# MCU.net
KiCad netlist of a schematic drawn in Altium Designer
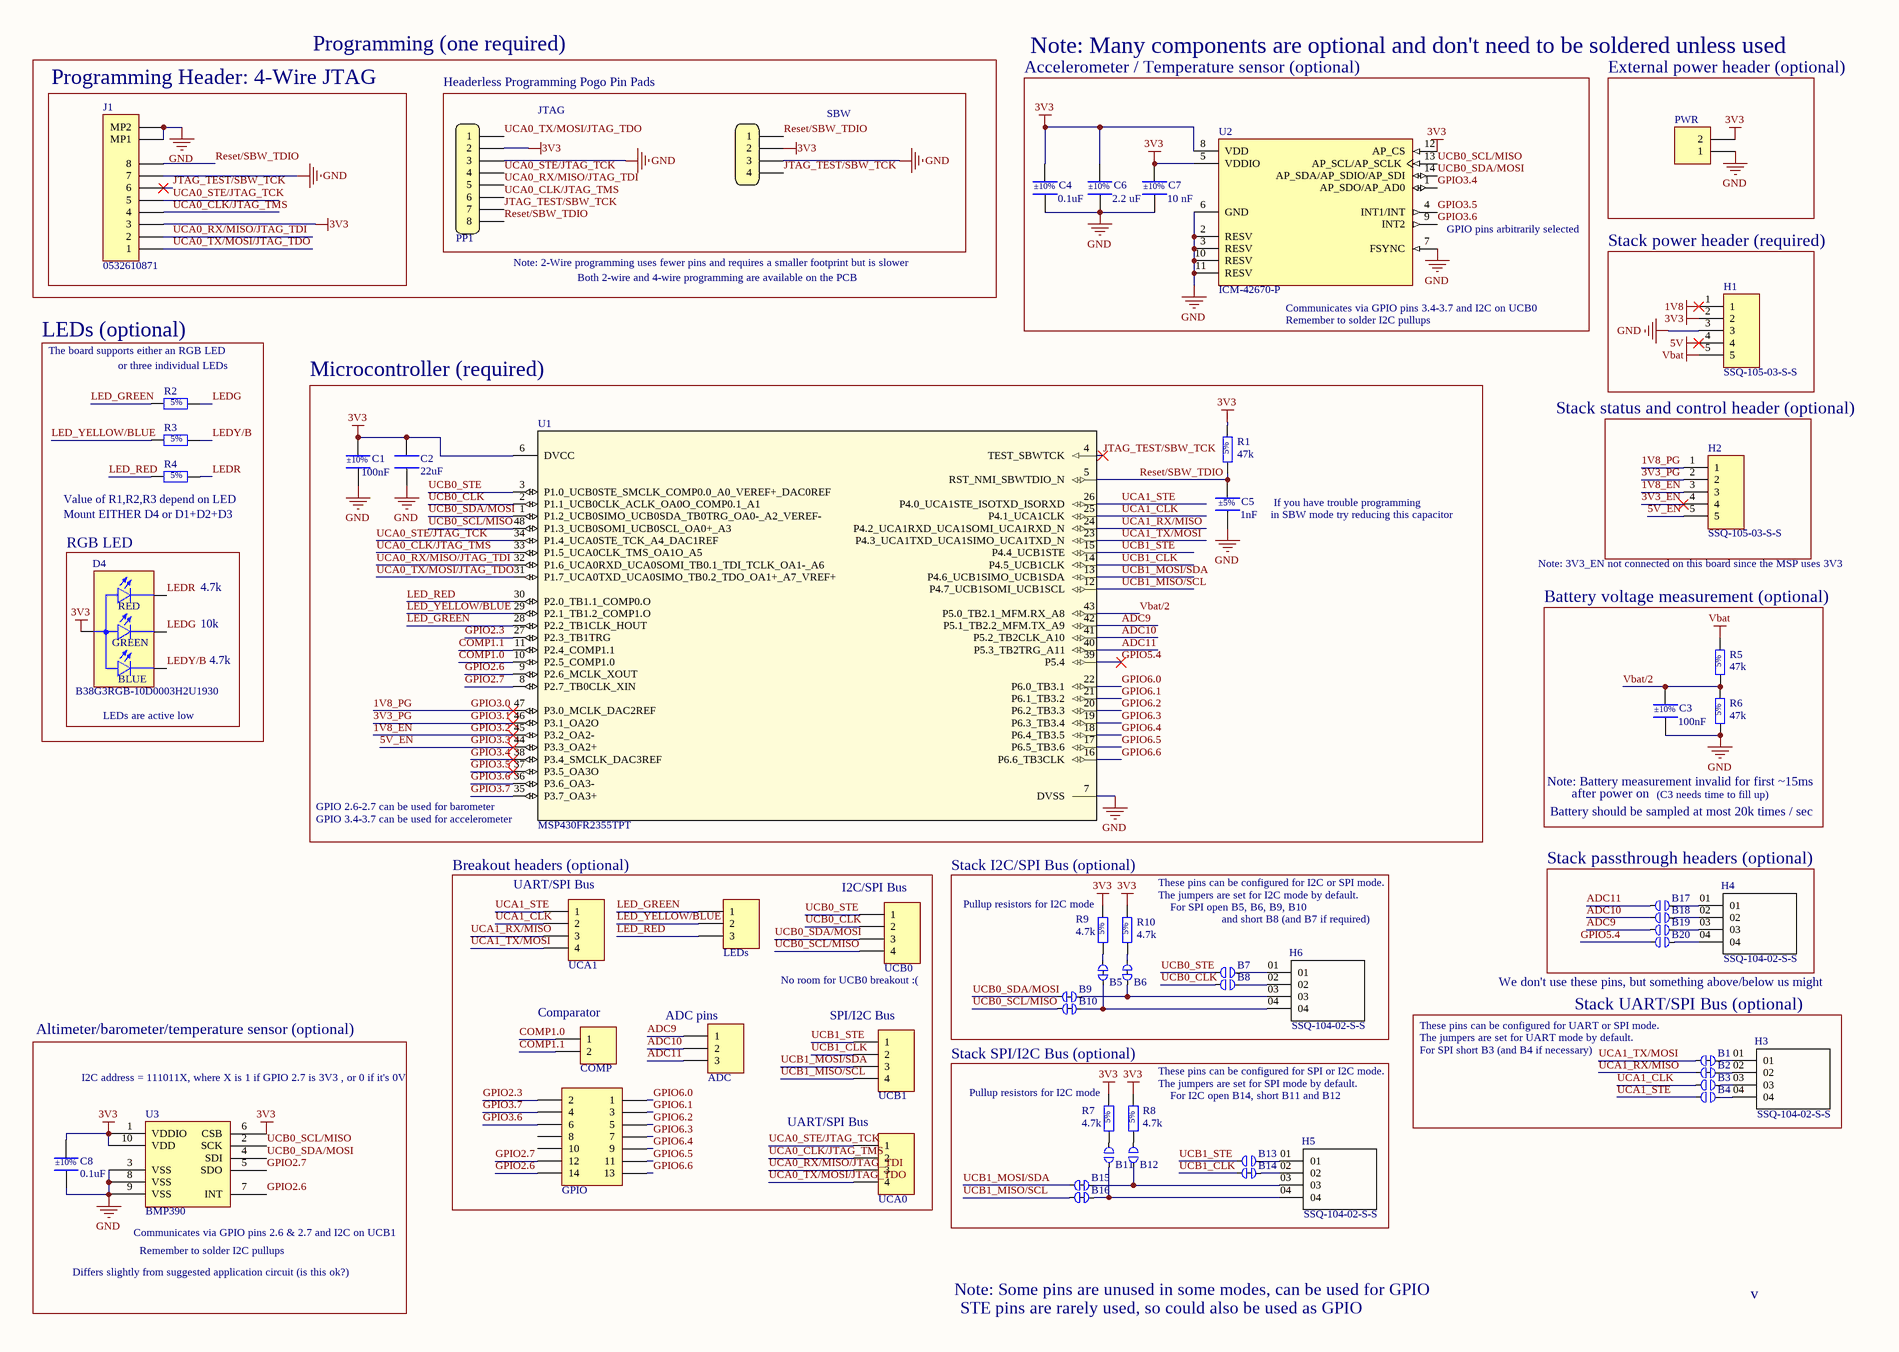
[diagram p0: MCU.SchDoc, left]
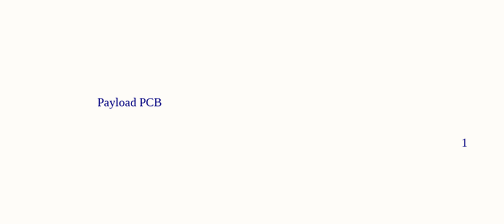
[diagram p1: MCU.SchDoc, right]

(export (version "E")
  (design (tool "Eeschema 10.0.6"))
  (components
    (comp (ref "ADC")
      (value "Header 3")
      (footprint "HDR1X3")
      (description "Header, 3-Pin")
      (libsource (lib "Miscellaneous Connectors") (part "Header 3"))
    )
    (comp (ref "B1")
      (value "Solder Jumper Normally Closed 0201")
      (footprint "Solder Bridge Closed 0201")
      (libsource (lib "APSS Generic Components") (part "Solder Jumper Normally Closed 0201"))
    )
    (comp (ref "B2")
      (value "Solder Jumper Normally Closed 0201")
      (footprint "Solder Bridge Closed 0201")
      (libsource (lib "APSS Generic Components") (part "Solder Jumper Normally Closed 0201"))
    )
    (comp (ref "B3")
      (value "Solder Jumper Normally Open 0201")
      (footprint "Solder Bridge Open 0201")
      (libsource (lib "APSS Generic Components") (part "Solder Jumper Normally Open 0201"))
    )
    (comp (ref "B4")
      (value "Solder Jumper Normally Open 0201")
      (footprint "Solder Bridge Open 0201")
      (libsource (lib "APSS Generic Components") (part "Solder Jumper Normally Open 0201"))
    )
    (comp (ref "B5")
      (value "Solder Jumper Normally Closed 0201")
      (footprint "Solder Bridge Closed 0201")
      (libsource (lib "APSS Generic Components") (part "Solder Jumper Normally Closed 0201"))
    )
    (comp (ref "B6")
      (value "Solder Jumper Normally Closed 0201")
      (footprint "Solder Bridge Closed 0201")
      (libsource (lib "APSS Generic Components") (part "Solder Jumper Normally Closed 0201"))
    )
    (comp (ref "B7")
      (value "Solder Jumper Normally Open 0201")
      (footprint "Solder Bridge Open 0201")
      (libsource (lib "") (part "Solder Jumper Normally Open 0201_1"))
    )
    (comp (ref "B8")
      (value "Solder Jumper Normally Open 0201")
      (footprint "Solder Bridge Open 0201")
      (libsource (lib "") (part "Solder Jumper Normally Open 0201_1"))
    )
    (comp (ref "B9")
      (value "Solder Jumper Normally Closed 0201")
      (footprint "Solder Bridge Closed 0201")
      (libsource (lib "APSS Generic Components") (part "Solder Jumper Normally Closed 0201"))
    )
    (comp (ref "B10")
      (value "Solder Jumper Normally Closed 0201")
      (footprint "Solder Bridge Closed 0201")
      (libsource (lib "APSS Generic Components") (part "Solder Jumper Normally Closed 0201"))
    )
    (comp (ref "B11")
      (value "Solder Jumper Normally Open 0201")
      (footprint "Solder Bridge Open 0201")
      (libsource (lib "APSS Generic Components") (part "Solder Jumper Normally Open 0201"))
    )
    (comp (ref "B12")
      (value "Solder Jumper Normally Open 0201")
      (footprint "Solder Bridge Open 0201")
      (libsource (lib "APSS Generic Components") (part "Solder Jumper Normally Open 0201"))
    )
    (comp (ref "B13")
      (value "Solder Jumper Normally Open 0201")
      (footprint "Solder Bridge Open 0201")
      (libsource (lib "APSS Generic Components") (part "Solder Jumper Normally Open 0201"))
    )
    (comp (ref "B14")
      (value "Solder Jumper Normally Closed 0201")
      (footprint "Solder Bridge Closed 0201")
      (libsource (lib "APSS Generic Components") (part "Solder Jumper Normally Closed 0201"))
    )
    (comp (ref "B15")
      (value "Solder Jumper Normally Closed 0201")
      (footprint "Solder Bridge Closed 0201")
      (libsource (lib "APSS Generic Components") (part "Solder Jumper Normally Closed 0201"))
    )
    (comp (ref "B16")
      (value "Solder Jumper Normally Closed 0201")
      (footprint "Solder Bridge Closed 0201")
      (libsource (lib "APSS Generic Components") (part "Solder Jumper Normally Closed 0201"))
    )
    (comp (ref "B17")
      (value "Solder Jumper Normally Open 0201")
      (footprint "Solder Bridge Open 0201")
      (libsource (lib "APSS Generic Components") (part "Solder Jumper Normally Open 0201"))
    )
    (comp (ref "B18")
      (value "Solder Jumper Normally Open 0201")
      (footprint "Solder Bridge Open 0201")
      (libsource (lib "APSS Generic Components") (part "Solder Jumper Normally Open 0201"))
    )
    (comp (ref "B19")
      (value "Solder Jumper Normally Open 0201")
      (footprint "Solder Bridge Open 0201")
      (libsource (lib "APSS Generic Components") (part "Solder Jumper Normally Open 0201"))
    )
    (comp (ref "B20")
      (value "Solder Jumper Normally Open 0201")
      (footprint "Solder Bridge Open 0201")
      (libsource (lib "APSS Generic Components") (part "Solder Jumper Normally Open 0201"))
    )
    (comp (ref "C1")
      (value "100nF")
      (footprint "APSS Generic Components:CAPACITOR_0805_2012M-70N")
      (description "Generic Capacitor")
      (fields (field (name "TOLERANCE") "±10%") (field (name "MF PART NO.") "C0805C104K5RAC7800"))
      (libsource (lib "General Components") (part "Generic Capacitor"))
    )
    (comp (ref "C2")
      (value "22uF")
      (footprint "APSS Prototype Parts:CAPACITOR_0805_2012M-70N")
      (description "Passive - Capacitor, X5R, 22uF Max, 6.3V, 0805 (2012 Metric), ±20%, -55°C ~ 85°C. 8.8uF @ 5V")
      (fields (field (name "TOLERANCE") "±20%") (field (name "MF PART NO.") "C0805C226M9PACTU"))
      (libsource (lib "APSS Prototype Parts") (part "C0805C226M9PACTU"))
    )
    (comp (ref "C3")
      (value "100nF")
      (footprint "APSS Generic Components:CAPACITOR_0805_2012M-70N")
      (description "Generic Capacitor")
      (fields (field (name "TOLERANCE") "±10%") (field (name "MF PART NO.") "C0805C104K5RAC7800"))
      (libsource (lib "APSS Generic Components") (part "Generic Capacitor"))
    )
    (comp (ref "C4")
      (value "0.1uF")
      (footprint "APSS Generic Components:CAPACITOR_0805_2012M-70N")
      (description "Generic Capacitor")
      (fields (field (name "TOLERANCE") "±10%") (field (name "MF PART NO.") "C0805C104K5RAC7800"))
      (libsource (lib "APSS Generic Components") (part "Generic Capacitor"))
    )
    (comp (ref "C5")
      (value "1nF")
      (footprint "APSS Generic Components:CAPACITOR_0805_2012M-70N")
      (description "Generic Capacitor")
      (fields (field (name "TOLERANCE") "±5%") (field (name "MF PART NO.") "399-C0805C102J5GAC7800CT-ND"))
      (libsource (lib "APSS Generic Components") (part "Generic Capacitor"))
    )
    (comp (ref "C6")
      (value "2.2 uF")
      (footprint "APSS Generic Components:CAPACITOR_0805_2012M-70N")
      (description "Generic Capacitor")
      (fields (field (name "TOLERANCE") "±10%") (field (name "MF PART NO.") "C0805C104K5RAC7800"))
      (libsource (lib "APSS Generic Components") (part "Generic Capacitor"))
    )
    (comp (ref "C7")
      (value "10 nF")
      (footprint "APSS Generic Components:CAPACITOR_0805_2012M-70N")
      (description "Generic Capacitor")
      (fields (field (name "TOLERANCE") "±10%") (field (name "MF PART NO.") "C0805C104K5RAC7800"))
      (libsource (lib "APSS Generic Components") (part "Generic Capacitor"))
    )
    (comp (ref "C8")
      (value "0.1uF")
      (footprint "APSS Generic Components:CAPACITOR_0805_2012M-70N")
      (description "Generic Capacitor")
      (fields (field (name "TOLERANCE") "±10%") (field (name "MF PART NO.") "C0805C104K5RAC7800"))
      (libsource (lib "APSS Generic Components") (part "Generic Capacitor"))
    )
    (comp (ref "COMP")
      (value "Header 2")
      (footprint "HDR1X2")
      (description "Header, 2-Pin")
      (libsource (lib "") (part "Header 2_1"))
    )
    (comp (ref "D4")
      (value "B38G3RGB-10D0003H2U1930")
      (footprint "APSS Prototype Parts:LED_B38G3RGB-10D0003H2U1930_0606_1616M")
      (description "Diode - LED, RGB, 2V Red, 3V Green, 3V Blue 0606 (1616 Metric)")
      (fields (field (name "APSS STANDARD PART") "APSS Standard"))
      (libsource (lib "APSS Prototype Parts") (part "B38G3RGB-10D0003H2U1930"))
    )
    (comp (ref "GPIO")
      (value "Header 7X2")
      (footprint "HDR2X7")
      (description "Header, 7-Pin, Dual row")
      (libsource (lib "Miscellaneous Connectors") (part "Header 7X2"))
    )
    (comp (ref "H1")
      (value "SSQ-105-03-S-S")
      (footprint "SAMTEC_SSQ-105-03-S-S:SAMTEC_SSQ-105-03-S-S")
      (libsource (lib "SSQ-105-03-S-S") (part "SSQ-105-03-S-S"))
    )
    (comp (ref "H2")
      (value "SSQ-105-03-S-S")
      (footprint "SAMTEC_SSQ-105-03-S-S:SAMTEC_SSQ-105-03-S-S")
      (libsource (lib "SSQ-105-03-S-S") (part "SSQ-105-03-S-S"))
    )
    (comp (ref "H3")
      (value "SSQ-104-02-S-S")
      (footprint "*SAMTEC_SSQ-104-02-S-S_SSQ-104-02-S-S(Primary)")
      (libsource (lib "SSQ-104-02-S-S") (part "SSQ-104-02-S-S"))
    )
    (comp (ref "H4")
      (value "SSQ-104-02-S-S")
      (footprint "*SAMTEC_SSQ-104-02-S-S_SSQ-104-02-S-S(Primary)")
      (libsource (lib "SSQ-104-02-S-S") (part "SSQ-104-02-S-S"))
    )
    (comp (ref "H5")
      (value "SSQ-104-02-S-S")
      (footprint "*SAMTEC_SSQ-104-02-S-S_SSQ-104-02-S-S(Primary)")
      (libsource (lib "SSQ-104-02-S-S") (part "SSQ-104-02-S-S"))
    )
    (comp (ref "H6")
      (value "SSQ-104-02-S-S")
      (footprint "*SAMTEC_SSQ-104-02-S-S_SSQ-104-02-S-S(Primary)")
      (libsource (lib "SSQ-104-02-S-S") (part "SSQ-104-02-S-S"))
    )
    (comp (ref "J1")
      (value "0532610871")
      (footprint "APSS Prototype Parts:MOLEX_0532610871")
      (description "Header - Picoblade 08-pin, SMT, RA")
      (fields (field (name "MF PART NO.") "0532610871") (field (name "APSS STANDARD PART") "APSS Standard"))
      (libsource (lib "APSS Prototype Parts") (part "0532610871"))
    )
    (comp (ref "LEDs")
      (value "Header 3")
      (footprint "HDR1X3")
      (description "Header, 3-Pin")
      (libsource (lib "Miscellaneous Connectors") (part "Header 3"))
    )
    (comp (ref "PP1")
      (value "Headerless Pogo Holes 8-pin")
      (footprint "POGO_8_PIN_HEADER")
      (libsource (lib "APSS Generic Components") (part "Headerless Pogo Holes 8-pin"))
    )
    (comp (ref "PP2")
      (value "Headerless Pogo Holes 4-pin")
      (footprint "APSS Generic Components:POGO_4_PIN_HEADER")
      (libsource (lib "APSS Generic Components") (part "Headerless Pogo Holes 4-pin"))
    )
    (comp (ref "PWR")
      (value "~")
      (footprint "HDR1X2")
      (description "Header, 2-Pin")
      (libsource (lib "Miscellaneous Connectors") (part "Header 2"))
    )
    (comp (ref "R1")
      (value "47k")
      (footprint "APSS Flight Parts:Resistor_0805_2012M-50N")
      (fields
        (field (name "TOLERANCE") "5%")
        (field (name "POWER") "1/8W")
        (field (name "MF PART NO.") "RMCF0805JT47K0")
      )
      (libsource (lib "APSS Prototype Parts") (part "RMCF0805JT Series"))
    )
    (comp (ref "R2")
      (value "1k")
      (footprint "APSS Flight Parts:Resistor_0805_2012M-50N")
      (fields
        (field (name "TOLERANCE") "5%")
        (field (name "POWER") "1/8W")
        (field (name "MF PART NO.") "RMCF0805JT1K00")
      )
      (libsource (lib "") (part "RMCF0805JT Series_1"))
    )
    (comp (ref "R3")
      (value "1k")
      (footprint "APSS Flight Parts:Resistor_0805_2012M-50N")
      (fields
        (field (name "TOLERANCE") "5%")
        (field (name "POWER") "1/8W")
        (field (name "MF PART NO.") "RMCF0805JT1K00")
      )
      (libsource (lib "") (part "RMCF0805JT Series_1"))
    )
    (comp (ref "R4")
      (value "1k")
      (footprint "APSS Flight Parts:Resistor_0805_2012M-50N")
      (fields
        (field (name "TOLERANCE") "5%")
        (field (name "POWER") "1/8W")
        (field (name "MF PART NO.") "RMCF0805JT1K00")
      )
      (libsource (lib "") (part "RMCF0805JT Series_1"))
    )
    (comp (ref "R5")
      (value "47k")
      (footprint "APSS Flight Parts:Resistor_0805_2012M-50N")
      (fields
        (field (name "TOLERANCE") "5%")
        (field (name "POWER") "1/8W")
        (field (name "MF PART NO.") "RMCF0805JT147K0")
      )
      (libsource (lib "APSS Prototype Parts") (part "RMCF0805JT Series"))
    )
    (comp (ref "R6")
      (value "47k")
      (footprint "APSS Flight Parts:Resistor_0805_2012M-50N")
      (fields
        (field (name "TOLERANCE") "5%")
        (field (name "POWER") "1/8W")
        (field (name "MF PART NO.") "RMCF0805JT47K0")
      )
      (libsource (lib "APSS Prototype Parts") (part "RMCF0805JT Series"))
    )
    (comp (ref "R7")
      (value "4.7k")
      (footprint "APSS Flight Parts:Resistor_0805_2012M-50N")
      (fields
        (field (name "TOLERANCE") "5%")
        (field (name "POWER") "1/8W")
        (field (name "MF PART NO.") "RMCF0805JT4K70")
      )
      (libsource (lib "APSS Prototype Parts") (part "RMCF0805JT Series"))
    )
    (comp (ref "R8")
      (value "4.7k")
      (footprint "APSS Flight Parts:Resistor_0805_2012M-50N")
      (fields
        (field (name "TOLERANCE") "5%")
        (field (name "POWER") "1/8W")
        (field (name "MF PART NO.") "RMCF0805JT4K70")
      )
      (libsource (lib "APSS Prototype Parts") (part "RMCF0805JT Series"))
    )
    (comp (ref "R9")
      (value "4.7k")
      (footprint "APSS Flight Parts:Resistor_0805_2012M-50N")
      (fields
        (field (name "TOLERANCE") "5%")
        (field (name "POWER") "1/8W")
        (field (name "MF PART NO.") "RMCF0805JT4K70")
      )
      (libsource (lib "APSS Prototype Parts") (part "RMCF0805JT Series"))
    )
    (comp (ref "R10")
      (value "4.7k")
      (footprint "APSS Flight Parts:Resistor_0805_2012M-50N")
      (fields
        (field (name "TOLERANCE") "5%")
        (field (name "POWER") "1/8W")
        (field (name "MF PART NO.") "RMCF0805JT4K70")
      )
      (libsource (lib "APSS Prototype Parts") (part "RMCF0805JT Series"))
    )
    (comp (ref "U1")
      (value "MSP430FR2355TPT")
      (footprint "PT0048A_L")
      (fields (field (name "APSS STANDARD PART") "APSS Standard"))
      (libsource (lib "MSP430") (part "MSP430FR2355IPT"))
    )
    (comp (ref "U2")
      (value "ICM-42670-P")
      (footprint "APSS Prototype Parts:XDCR_ICM-42670-P-EXTENDED_PADS")
      (fields (field (name "APSS STANDARD PART") "APSS Standard"))
      (libsource (lib "APSS Prototype Parts") (part "ICM-42670-P"))
    )
    (comp (ref "U3")
      (value "BMP390")
      (footprint "BMP390")
      (description "Digital Pressure Sensor")
      (libsource (lib "APSS Prototype Parts") (part "BMP390"))
    )
    (comp (ref "UCA0")
      (value "Header 4")
      (footprint "HDR1X4")
      (description "Header, 4-Pin")
      (libsource (lib "Miscellaneous Connectors") (part "Header 4"))
    )
    (comp (ref "UCA1")
      (value "Header 4")
      (footprint "HDR1X4")
      (description "Header, 4-Pin")
      (libsource (lib "Miscellaneous Connectors") (part "Header 4"))
    )
    (comp (ref "UCB0")
      (value "Header 4")
      (footprint "HDR1X4")
      (description "Header, 4-Pin")
      (libsource (lib "Miscellaneous Connectors") (part "Header 4"))
    )
    (comp (ref "UCB1")
      (value "Header 4")
      (footprint "HDR1X4")
      (description "Header, 4-Pin")
      (libsource (lib "Miscellaneous Connectors") (part "Header 4"))
    )
  )
  (nets
    (net (code "1") (name "/1V8_EN") (class "Default")
      (node (ref "H2") (pin "3") (pinfunction "3_3") (pintype "passive"))
      (node (ref "U1") (pin "45") (pinfunction "P3.2_OA2-_45") (pintype "bidirectional"))
    )
    (net (code "2") (name "/1V8_PG") (class "Default")
      (node (ref "H2") (pin "1") (pinfunction "1_1") (pintype "passive"))
      (node (ref "U1") (pin "47") (pinfunction "P3.0_MCLK_DAC2REF_47") (pintype "bidirectional"))
    )
    (net (code "3") (name "/3V3_EN") (class "Default")
      (node (ref "H2") (pin "4") (pinfunction "4_4") (pintype "passive+no_connect"))
    )
    (net (code "4") (name "/3V3_PG") (class "Default")
      (node (ref "H2") (pin "2") (pinfunction "2_2") (pintype "passive"))
      (node (ref "U1") (pin "46") (pinfunction "P3.1_OA2O_46") (pintype "bidirectional"))
    )
    (net (code "5") (name "/5V_EN") (class "Default")
      (node (ref "H2") (pin "5") (pinfunction "5_5") (pintype "passive"))
      (node (ref "U1") (pin "44") (pinfunction "P3.3_OA2+_44") (pintype "bidirectional"))
    )
    (net (code "7") (name "/ADC9") (class "Default")
      (node (ref "ADC") (pin "1") (pinfunction "1_1") (pintype "passive"))
      (node (ref "B19") (pin "1") (pinfunction "1_1") (pintype "passive"))
      (node (ref "U1") (pin "42") (pinfunction "P5.1_TB2.2_MFM.TX_A9_42") (pintype "bidirectional"))
    )
    (net (code "8") (name "/ADC10") (class "Default")
      (node (ref "ADC") (pin "2") (pinfunction "2_2") (pintype "passive"))
      (node (ref "B18") (pin "1") (pinfunction "1_1") (pintype "passive"))
      (node (ref "U1") (pin "41") (pinfunction "P5.2_TB2CLK_A10_41") (pintype "bidirectional"))
    )
    (net (code "9") (name "/ADC11") (class "Default")
      (node (ref "ADC") (pin "3") (pinfunction "3_3") (pintype "passive"))
      (node (ref "B17") (pin "1") (pinfunction "1_1") (pintype "passive"))
      (node (ref "U1") (pin "40") (pinfunction "P5.3_TB2TRG_A11_40") (pintype "bidirectional"))
    )
    (net (code "10") (name "/COMP1.0") (class "Default")
      (node (ref "COMP") (pin "1") (pinfunction "1_1") (pintype "passive"))
      (node (ref "U1") (pin "10") (pinfunction "P2.5_COMP1.0_10") (pintype "bidirectional"))
    )
    (net (code "11") (name "/COMP1.1") (class "Default")
      (node (ref "COMP") (pin "2") (pinfunction "2_2") (pintype "passive"))
      (node (ref "U1") (pin "11") (pinfunction "P2.4_COMP1.1_11") (pintype "bidirectional"))
    )
    (net (code "12") (name "/GPIO2.3") (class "Default")
      (node (ref "GPIO") (pin "2") (pinfunction "2_2") (pintype "passive"))
      (node (ref "U1") (pin "27") (pinfunction "P2.3_TB1TRG_27") (pintype "bidirectional"))
    )
    (net (code "13") (name "/GPIO2.6") (class "Default")
      (node (ref "GPIO") (pin "14") (pinfunction "14_14") (pintype "passive"))
      (node (ref "U1") (pin "9") (pinfunction "P2.6_MCLK_XOUT_9") (pintype "bidirectional"))
      (node (ref "U3") (pin "7") (pinfunction "INT_7") (pintype "passive"))
    )
    (net (code "14") (name "/GPIO2.7") (class "Default")
      (node (ref "GPIO") (pin "12") (pinfunction "12_12") (pintype "passive"))
      (node (ref "U1") (pin "8") (pinfunction "P2.7_TB0CLK_XIN_8") (pintype "bidirectional"))
      (node (ref "U3") (pin "5") (pinfunction "SDO_5") (pintype "passive"))
    )
    (net (code "15") (name "/GPIO3.4") (class "Default")
      (node (ref "U1") (pin "38") (pinfunction "P3.4_SMCLK_DAC3REF_38") (pintype "bidirectional"))
      (node (ref "U2") (pin "1") (pinfunction "AP_SDO/AP_AD0_1") (pintype "bidirectional"))
    )
    (net (code "16") (name "/GPIO3.5") (class "Default")
      (node (ref "U1") (pin "37") (pinfunction "P3.5_OA3O_37") (pintype "bidirectional"))
      (node (ref "U2") (pin "4") (pinfunction "INT1/INT_4") (pintype "output"))
    )
    (net (code "17") (name "/GPIO3.6") (class "Default")
      (node (ref "GPIO") (pin "6") (pinfunction "6_6") (pintype "passive"))
      (node (ref "U1") (pin "36") (pinfunction "P3.6_OA3-_36") (pintype "bidirectional"))
      (node (ref "U2") (pin "9") (pinfunction "INT2_9") (pintype "output"))
    )
    (net (code "18") (name "/GPIO3.7") (class "Default")
      (node (ref "GPIO") (pin "4") (pinfunction "4_4") (pintype "passive"))
      (node (ref "U1") (pin "35") (pinfunction "P3.7_OA3+_35") (pintype "bidirectional"))
    )
    (net (code "19") (name "/GPIO5.4") (class "Default")
      (node (ref "B20") (pin "1") (pinfunction "1_1") (pintype "passive"))
      (node (ref "U1") (pin "39") (pinfunction "P5.4_39") (pintype "bidirectional"))
    )
    (net (code "20") (name "/GPIO6.0") (class "Default")
      (node (ref "GPIO") (pin "1") (pinfunction "1_1") (pintype "passive"))
      (node (ref "U1") (pin "22") (pinfunction "P6.0_TB3.1_22") (pintype "bidirectional"))
    )
    (net (code "21") (name "/GPIO6.1") (class "Default")
      (node (ref "GPIO") (pin "3") (pinfunction "3_3") (pintype "passive"))
      (node (ref "U1") (pin "21") (pinfunction "P6.1_TB3.2_21") (pintype "bidirectional"))
    )
    (net (code "22") (name "/GPIO6.2") (class "Default")
      (node (ref "GPIO") (pin "5") (pinfunction "5_5") (pintype "passive"))
      (node (ref "U1") (pin "20") (pinfunction "P6.2_TB3.3_20") (pintype "bidirectional"))
    )
    (net (code "23") (name "/GPIO6.3") (class "Default")
      (node (ref "GPIO") (pin "7") (pinfunction "7_7") (pintype "passive"))
      (node (ref "U1") (pin "19") (pinfunction "P6.3_TB3.4_19") (pintype "bidirectional"))
    )
    (net (code "24") (name "/GPIO6.4") (class "Default")
      (node (ref "GPIO") (pin "9") (pinfunction "9_9") (pintype "passive"))
      (node (ref "U1") (pin "18") (pinfunction "P6.4_TB3.5_18") (pintype "bidirectional"))
    )
    (net (code "25") (name "/GPIO6.5") (class "Default")
      (node (ref "GPIO") (pin "11") (pinfunction "11_11") (pintype "passive"))
      (node (ref "U1") (pin "17") (pinfunction "P6.5_TB3.6_17") (pintype "bidirectional"))
    )
    (net (code "26") (name "/GPIO6.6") (class "Default")
      (node (ref "GPIO") (pin "13") (pinfunction "13_13") (pintype "passive"))
      (node (ref "U1") (pin "16") (pinfunction "P6.6_TB3CLK_16") (pintype "bidirectional"))
    )
    (net (code "27") (name "/JTAG_TEST{slash}SBW_TCK") (class "Default")
      (node (ref "J1") (pin "6") (pinfunction "6_6") (pintype "passive"))
      (node (ref "PP1") (pin "7") (pinfunction "7_7") (pintype "passive"))
      (node (ref "PP2") (pin "4") (pinfunction "4_4") (pintype "passive"))
      (node (ref "U1") (pin "4") (pinfunction "TEST_SBWTCK_4") (pintype "input"))
    )
    (net (code "28") (name "/LEDG") (class "Default")
      (node (ref "D4") (pin "1") (pinfunction "G_C_1") (pintype "passive"))
      (node (ref "R2") (pin "2") (pinfunction "2_2") (pintype "passive"))
    )
    (net (code "29") (name "/LEDR") (class "Default")
      (node (ref "D4") (pin "4") (pinfunction "R_C_4") (pintype "passive"))
      (node (ref "R4") (pin "2") (pinfunction "2_2") (pintype "passive"))
    )
    (net (code "30") (name "/LEDY{slash}B") (class "Default")
      (node (ref "D4") (pin "2") (pinfunction "B_C_2") (pintype "passive"))
      (node (ref "R3") (pin "2") (pinfunction "2_2") (pintype "passive"))
    )
    (net (code "31") (name "/LED_GREEN") (class "Default")
      (node (ref "LEDs") (pin "1") (pinfunction "1_1") (pintype "passive"))
      (node (ref "R2") (pin "1") (pinfunction "1_1") (pintype "passive"))
      (node (ref "U1") (pin "28") (pinfunction "P2.2_TB1CLK_HOUT_28") (pintype "bidirectional"))
    )
    (net (code "32") (name "/LED_RED") (class "Default")
      (node (ref "LEDs") (pin "3") (pinfunction "3_3") (pintype "passive"))
      (node (ref "R4") (pin "1") (pinfunction "1_1") (pintype "passive"))
      (node (ref "U1") (pin "30") (pinfunction "P2.0_TB1.1_COMP0.O_30") (pintype "bidirectional"))
    )
    (net (code "33") (name "/LED_YELLOW{slash}BLUE") (class "Default")
      (node (ref "LEDs") (pin "2") (pinfunction "2_2") (pintype "passive"))
      (node (ref "R3") (pin "1") (pinfunction "1_1") (pintype "passive"))
      (node (ref "U1") (pin "29") (pinfunction "P2.1_TB1.2_COMP1.O_29") (pintype "bidirectional"))
    )
    (net (code "34") (name "/Reset{slash}SBW_TDIO") (class "Default")
      (node (ref "C5") (pin "2") (pinfunction "2_2") (pintype "passive"))
      (node (ref "J1") (pin "8") (pinfunction "8_8") (pintype "passive"))
      (node (ref "PP1") (pin "8") (pinfunction "8_8") (pintype "passive"))
      (node (ref "PP2") (pin "1") (pinfunction "1_1") (pintype "passive"))
      (node (ref "R1") (pin "1") (pinfunction "1_1") (pintype "passive"))
      (node (ref "U1") (pin "5") (pinfunction "RST_NMI_SBWTDIO_N_5") (pintype "bidirectional"))
    )
    (net (code "35") (name "/UCA0_CLK{slash}JTAG_TMS") (class "Default")
      (node (ref "J1") (pin "4") (pinfunction "4_4") (pintype "passive"))
      (node (ref "PP1") (pin "6") (pinfunction "6_6") (pintype "passive"))
      (node (ref "U1") (pin "33") (pinfunction "P1.5_UCA0CLK_TMS_OA1O_A5_33") (pintype "bidirectional"))
      (node (ref "UCA0") (pin "2") (pinfunction "2_2") (pintype "passive"))
    )
    (net (code "36") (name "/UCA0_RX{slash}MISO{slash}JTAG_TDI") (class "Default")
      (node (ref "J1") (pin "2") (pinfunction "2_2") (pintype "passive"))
      (node (ref "PP1") (pin "5") (pinfunction "5_5") (pintype "passive"))
      (node (ref "U1") (pin "32") (pinfunction "P1.6_UCA0RXD_UCA0SOMI_TB0.1_TDI_TCLK_OA1-_A6_32") (pintype "bidirectional"))
      (node (ref "UCA0") (pin "3") (pinfunction "3_3") (pintype "passive"))
    )
    (net (code "37") (name "/UCA0_STE{slash}JTAG_TCK") (class "Default")
      (node (ref "J1") (pin "5") (pinfunction "5_5") (pintype "passive"))
      (node (ref "PP1") (pin "4") (pinfunction "4_4") (pintype "passive"))
      (node (ref "U1") (pin "34") (pinfunction "P1.4_UCA0STE_TCK_A4_DAC1REF_34") (pintype "bidirectional"))
      (node (ref "UCA0") (pin "1") (pinfunction "1_1") (pintype "passive"))
    )
    (net (code "38") (name "/UCA0_TX{slash}MOSI{slash}JTAG_TDO") (class "Default")
      (node (ref "J1") (pin "1") (pinfunction "1_1") (pintype "passive"))
      (node (ref "PP1") (pin "1") (pinfunction "1_1") (pintype "passive"))
      (node (ref "U1") (pin "31") (pinfunction "P1.7_UCA0TXD_UCA0SIMO_TB0.2_TDO_OA1+_A7_VREF+_31") (pintype "bidirectional"))
      (node (ref "UCA0") (pin "4") (pinfunction "4_4") (pintype "passive"))
    )
    (net (code "39") (name "/UCA1_CLK") (class "Default")
      (node (ref "B3") (pin "1") (pinfunction "1_1") (pintype "passive"))
      (node (ref "U1") (pin "25") (pinfunction "P4.1_UCA1CLK_25") (pintype "bidirectional"))
      (node (ref "UCA1") (pin "2") (pinfunction "2_2") (pintype "passive"))
    )
    (net (code "40") (name "/UCA1_RX{slash}MISO") (class "Default")
      (node (ref "B2") (pin "1") (pinfunction "1_1") (pintype "passive"))
      (node (ref "U1") (pin "24") (pinfunction "P4.2_UCA1RXD_UCA1SOMI_UCA1RXD_N_24") (pintype "bidirectional"))
      (node (ref "UCA1") (pin "3") (pinfunction "3_3") (pintype "passive"))
    )
    (net (code "41") (name "/UCA1_STE") (class "Default")
      (node (ref "B4") (pin "1") (pinfunction "1_1") (pintype "passive"))
      (node (ref "U1") (pin "26") (pinfunction "P4.0_UCA1STE_ISOTXD_ISORXD_26") (pintype "bidirectional"))
      (node (ref "UCA1") (pin "1") (pinfunction "1_1") (pintype "passive"))
    )
    (net (code "42") (name "/UCA1_TX{slash}MOSI") (class "Default")
      (node (ref "B1") (pin "1") (pinfunction "1_1") (pintype "passive"))
      (node (ref "U1") (pin "23") (pinfunction "P4.3_UCA1TXD_UCA1SIMO_UCA1TXD_N_23") (pintype "bidirectional"))
      (node (ref "UCA1") (pin "4") (pinfunction "4_4") (pintype "passive"))
    )
    (net (code "43") (name "/UCB0_CLK") (class "Default")
      (node (ref "B8") (pin "2") (pinfunction "2_2") (pintype "passive"))
      (node (ref "U1") (pin "2") (pinfunction "P1.1_UCB0CLK_ACLK_OA0O_COMP0.1_A1_2") (pintype "bidirectional"))
      (node (ref "UCB0") (pin "2") (pinfunction "2_2") (pintype "passive"))
    )
    (net (code "44") (name "/UCB0_SCL{slash}MISO") (class "Default")
      (node (ref "B10") (pin "1") (pinfunction "1_1") (pintype "passive"))
      (node (ref "U1") (pin "48") (pinfunction "P1.3_UCB0SOMI_UCB0SCL_OA0+_A3_48") (pintype "bidirectional"))
      (node (ref "U2") (pin "13") (pinfunction "AP_SCL/AP_SCLK_13") (pintype "input"))
      (node (ref "U3") (pin "2") (pinfunction "SCK_2") (pintype "passive"))
      (node (ref "UCB0") (pin "4") (pinfunction "4_4") (pintype "passive"))
    )
    (net (code "45") (name "/UCB0_SDA{slash}MOSI") (class "Default")
      (node (ref "B9") (pin "2") (pinfunction "2_2") (pintype "passive"))
      (node (ref "U1") (pin "1") (pinfunction "P1.2_UCB0SIMO_UCB0SDA_TB0TRG_OA0-_A2_VEREF-_1") (pintype "bidirectional"))
      (node (ref "U2") (pin "14") (pinfunction "AP_SDA/AP_SDIO/AP_SDI_14") (pintype "bidirectional"))
      (node (ref "U3") (pin "4") (pinfunction "SDI_4") (pintype "passive"))
      (node (ref "UCB0") (pin "3") (pinfunction "3_3") (pintype "passive"))
    )
    (net (code "46") (name "/UCB0_STE") (class "Default")
      (node (ref "B7") (pin "2") (pinfunction "2_2") (pintype "passive"))
      (node (ref "U1") (pin "3") (pinfunction "P1.0_UCB0STE_SMCLK_COMP0.0_A0_VEREF+_DAC0REF_3") (pintype "bidirectional"))
      (node (ref "UCB0") (pin "1") (pinfunction "1_1") (pintype "passive"))
    )
    (net (code "47") (name "/UCB1_CLK") (class "Default")
      (node (ref "B14") (pin "1") (pinfunction "1_1") (pintype "passive"))
      (node (ref "U1") (pin "14") (pinfunction "P4.5_UCB1CLK_14") (pintype "bidirectional"))
      (node (ref "UCB1") (pin "2") (pinfunction "2_2") (pintype "passive"))
    )
    (net (code "48") (name "/UCB1_MISO{slash}SCL") (class "Default")
      (node (ref "B16") (pin "1") (pinfunction "1_1") (pintype "passive"))
      (node (ref "U1") (pin "12") (pinfunction "P4.7_UCB1SOMI_UCB1SCL_12") (pintype "bidirectional"))
      (node (ref "UCB1") (pin "4") (pinfunction "4_4") (pintype "passive"))
    )
    (net (code "49") (name "/UCB1_MOSI{slash}SDA") (class "Default")
      (node (ref "B15") (pin "1") (pinfunction "1_1") (pintype "passive"))
      (node (ref "U1") (pin "13") (pinfunction "P4.6_UCB1SIMO_UCB1SDA_13") (pintype "bidirectional"))
      (node (ref "UCB1") (pin "3") (pinfunction "3_3") (pintype "passive"))
    )
    (net (code "50") (name "/UCB1_STE") (class "Default")
      (node (ref "B13") (pin "1") (pinfunction "1_1") (pintype "passive"))
      (node (ref "U1") (pin "15") (pinfunction "P4.4_UCB1STE_15") (pintype "bidirectional"))
      (node (ref "UCB1") (pin "1") (pinfunction "1_1") (pintype "passive"))
    )
    (net (code "51") (name "/Vbat{slash}2") (class "Default")
      (node (ref "C3") (pin "2") (pinfunction "2_2") (pintype "passive"))
      (node (ref "R5") (pin "1") (pinfunction "1_1") (pintype "passive"))
      (node (ref "R6") (pin "2") (pinfunction "2_2") (pintype "passive"))
      (node (ref "U1") (pin "43") (pinfunction "P5.0_TB2.1_MFM.RX_A8_43") (pintype "bidirectional"))
    )
    (net (code "52") (name "1V8") (class "Default")
      (node (ref "H1") (pin "1") (pinfunction "1_1") (pintype "passive"))
    )
    (net (code "53") (name "3V3") (class "Default")
      (node (ref "C1") (pin "2") (pinfunction "2_2") (pintype "passive"))
      (node (ref "C2") (pin "2") (pinfunction "2_2") (pintype "passive"))
      (node (ref "C4") (pin "2") (pinfunction "2_2") (pintype "passive"))
      (node (ref "C6") (pin "2") (pinfunction "2_2") (pintype "passive"))
      (node (ref "C7") (pin "2") (pinfunction "2_2") (pintype "passive"))
      (node (ref "C8") (pin "2") (pinfunction "2_2") (pintype "passive"))
      (node (ref "D4") (pin "3") (pinfunction "A_3") (pintype "passive"))
      (node (ref "H1") (pin "2") (pinfunction "2_2") (pintype "passive"))
      (node (ref "J1") (pin "3") (pinfunction "3_3") (pintype "passive"))
      (node (ref "PP1") (pin "2") (pinfunction "2_2") (pintype "passive"))
      (node (ref "PP2") (pin "2") (pinfunction "2_2") (pintype "passive"))
      (node (ref "PWR") (pin "2") (pinfunction "2_2") (pintype "passive"))
      (node (ref "R1") (pin "2") (pinfunction "2_2") (pintype "passive"))
      (node (ref "R10") (pin "2") (pinfunction "2_2") (pintype "passive"))
      (node (ref "R7") (pin "2") (pinfunction "2_2") (pintype "passive"))
      (node (ref "R8") (pin "2") (pinfunction "2_2") (pintype "passive"))
      (node (ref "R9") (pin "2") (pinfunction "2_2") (pintype "passive"))
      (node (ref "U1") (pin "6") (pinfunction "DVCC_6") (pintype "power_in"))
      (node (ref "U2") (pin "12") (pinfunction "AP_CS_12") (pintype "input"))
      (node (ref "U2") (pin "5") (pinfunction "VDDIO_5") (pintype "power_in"))
      (node (ref "U2") (pin "8") (pinfunction "VDD_8") (pintype "power_in"))
      (node (ref "U3") (pin "1") (pinfunction "VDDIO_1") (pintype "passive"))
      (node (ref "U3") (pin "10") (pinfunction "VDD_10") (pintype "passive"))
      (node (ref "U3") (pin "6") (pinfunction "CSB_6") (pintype "passive"))
    )
    (net (code "54") (name "5V") (class "Default")
      (node (ref "H1") (pin "4") (pinfunction "4_4") (pintype "passive"))
    )
    (net (code "55") (name "GND") (class "Default")
      (node (ref "C1") (pin "1") (pinfunction "1_1") (pintype "passive"))
      (node (ref "C2") (pin "1") (pinfunction "1_1") (pintype "passive"))
      (node (ref "C3") (pin "1") (pinfunction "1_1") (pintype "passive"))
      (node (ref "C4") (pin "1") (pinfunction "1_1") (pintype "passive"))
      (node (ref "C5") (pin "1") (pinfunction "1_1") (pintype "passive"))
      (node (ref "C6") (pin "1") (pinfunction "1_1") (pintype "passive"))
      (node (ref "C7") (pin "1") (pinfunction "1_1") (pintype "passive"))
      (node (ref "C8") (pin "1") (pinfunction "1_1") (pintype "passive"))
      (node (ref "H1") (pin "3") (pinfunction "3_3") (pintype "passive"))
      (node (ref "J1") (pin "7") (pinfunction "7_7") (pintype "passive"))
      (node (ref "J1") (pin "MP1") (pinfunction "MP1_MP1") (pintype "passive"))
      (node (ref "J1") (pin "MP2") (pinfunction "MP2_MP2") (pintype "passive"))
      (node (ref "PP1") (pin "3") (pinfunction "3_3") (pintype "passive"))
      (node (ref "PP2") (pin "3") (pinfunction "3_3") (pintype "passive"))
      (node (ref "PWR") (pin "1") (pinfunction "1_1") (pintype "passive"))
      (node (ref "R6") (pin "1") (pinfunction "1_1") (pintype "passive"))
      (node (ref "U1") (pin "7") (pinfunction "DVSS_7") (pintype "power_in"))
      (node (ref "U2") (pin "10") (pinfunction "RESV_10") (pintype "passive"))
      (node (ref "U2") (pin "11") (pinfunction "RESV_11") (pintype "passive"))
      (node (ref "U2") (pin "2") (pinfunction "RESV_2") (pintype "passive"))
      (node (ref "U2") (pin "3") (pinfunction "RESV_3") (pintype "passive"))
      (node (ref "U2") (pin "6") (pinfunction "GND_6") (pintype "power_in"))
      (node (ref "U2") (pin "7") (pinfunction "FSYNC_7") (pintype "input"))
      (node (ref "U3") (pin "3") (pinfunction "VSS_3") (pintype "passive"))
      (node (ref "U3") (pin "8") (pinfunction "VSS_8") (pintype "passive"))
      (node (ref "U3") (pin "9") (pinfunction "VSS_9") (pintype "passive"))
    )
    (net (code "56") (name "Net-(B1-Pad2)") (class "Default")
      (node (ref "B1") (pin "2") (pinfunction "2_2") (pintype "passive"))
      (node (ref "H3") (pin "01") (pinfunction "01_01") (pintype "passive"))
    )
    (net (code "57") (name "Net-(B2-Pad2)") (class "Default")
      (node (ref "B2") (pin "2") (pinfunction "2_2") (pintype "passive"))
      (node (ref "H3") (pin "02") (pinfunction "02_02") (pintype "passive"))
    )
    (net (code "58") (name "Net-(B3-Pad2)") (class "Default")
      (node (ref "B3") (pin "2") (pinfunction "2_2") (pintype "passive"))
      (node (ref "H3") (pin "03") (pinfunction "03_03") (pintype "passive"))
    )
    (net (code "59") (name "Net-(B4-Pad2)") (class "Default")
      (node (ref "B4") (pin "2") (pinfunction "2_2") (pintype "passive"))
      (node (ref "H3") (pin "04") (pinfunction "04_04") (pintype "passive"))
    )
    (net (code "60") (name "Net-(B5-Pad2)") (class "Default")
      (node (ref "B5") (pin "2") (pinfunction "2_2") (pintype "passive"))
      (node (ref "R9") (pin "1") (pinfunction "1_1") (pintype "passive"))
    )
    (net (code "61") (name "Net-(B6-Pad1)") (class "Default")
      (node (ref "B6") (pin "1") (pinfunction "1_1") (pintype "passive"))
      (node (ref "R10") (pin "1") (pinfunction "1_1") (pintype "passive"))
    )
    (net (code "62") (name "Net-(B6-Pad2)") (class "Default")
      (node (ref "B6") (pin "2") (pinfunction "2_2") (pintype "passive"))
      (node (ref "B9") (pin "1") (pinfunction "1_1") (pintype "passive"))
      (node (ref "H6") (pin "03") (pinfunction "03_03") (pintype "passive"))
    )
    (net (code "63") (name "Net-(B7-Pad1)") (class "Default")
      (node (ref "B7") (pin "1") (pinfunction "1_1") (pintype "passive"))
      (node (ref "H6") (pin "01") (pinfunction "01_01") (pintype "passive"))
    )
    (net (code "64") (name "Net-(B8-Pad1)") (class "Default")
      (node (ref "B8") (pin "1") (pinfunction "1_1") (pintype "passive"))
      (node (ref "H6") (pin "02") (pinfunction "02_02") (pintype "passive"))
    )
    (net (code "65") (name "Net-(B10-Pad2)") (class "Default")
      (node (ref "B10") (pin "2") (pinfunction "2_2") (pintype "passive"))
      (node (ref "B5") (pin "1") (pinfunction "1_1") (pintype "passive"))
      (node (ref "H6") (pin "04") (pinfunction "04_04") (pintype "passive"))
    )
    (net (code "66") (name "Net-(B11-Pad1)") (class "Default")
      (node (ref "B11") (pin "1") (pinfunction "1_1") (pintype "passive"))
      (node (ref "B16") (pin "2") (pinfunction "2_2") (pintype "passive"))
      (node (ref "H5") (pin "04") (pinfunction "04_04") (pintype "passive"))
    )
    (net (code "67") (name "Net-(B11-Pad2)") (class "Default")
      (node (ref "B11") (pin "2") (pinfunction "2_2") (pintype "passive"))
      (node (ref "R7") (pin "1") (pinfunction "1_1") (pintype "passive"))
    )
    (net (code "68") (name "Net-(B12-Pad1)") (class "Default")
      (node (ref "B12") (pin "1") (pinfunction "1_1") (pintype "passive"))
      (node (ref "R8") (pin "1") (pinfunction "1_1") (pintype "passive"))
    )
    (net (code "69") (name "Net-(B12-Pad2)") (class "Default")
      (node (ref "B12") (pin "2") (pinfunction "2_2") (pintype "passive"))
      (node (ref "B15") (pin "2") (pinfunction "2_2") (pintype "passive"))
      (node (ref "H5") (pin "03") (pinfunction "03_03") (pintype "passive"))
    )
    (net (code "70") (name "Net-(B13-Pad2)") (class "Default")
      (node (ref "B13") (pin "2") (pinfunction "2_2") (pintype "passive"))
      (node (ref "H5") (pin "01") (pinfunction "01_01") (pintype "passive"))
    )
    (net (code "71") (name "Net-(B14-Pad2)") (class "Default")
      (node (ref "B14") (pin "2") (pinfunction "2_2") (pintype "passive"))
      (node (ref "H5") (pin "02") (pinfunction "02_02") (pintype "passive"))
    )
    (net (code "72") (name "Net-(B17-Pad2)") (class "Default")
      (node (ref "B17") (pin "2") (pinfunction "2_2") (pintype "passive"))
      (node (ref "H4") (pin "01") (pinfunction "01_01") (pintype "passive"))
    )
    (net (code "73") (name "Net-(B18-Pad2)") (class "Default")
      (node (ref "B18") (pin "2") (pinfunction "2_2") (pintype "passive"))
      (node (ref "H4") (pin "02") (pinfunction "02_02") (pintype "passive"))
    )
    (net (code "74") (name "Net-(B19-Pad2)") (class "Default")
      (node (ref "B19") (pin "2") (pinfunction "2_2") (pintype "passive"))
      (node (ref "H4") (pin "03") (pinfunction "03_03") (pintype "passive"))
    )
    (net (code "75") (name "Net-(B20-Pad2)") (class "Default")
      (node (ref "B20") (pin "2") (pinfunction "2_2") (pintype "passive"))
      (node (ref "H4") (pin "04") (pinfunction "04_04") (pintype "passive"))
    )
    (net (code "76") (name "Vbat") (class "Default")
      (node (ref "H1") (pin "5") (pinfunction "5_5") (pintype "passive"))
      (node (ref "R5") (pin "2") (pinfunction "2_2") (pintype "passive"))
    )
    (net (code "77") (name "unconnected-(GPIO-Pad8)") (class "Default")
      (node (ref "GPIO") (pin "8") (pinfunction "8_8") (pintype "passive"))
    )
    (net (code "78") (name "unconnected-(GPIO-Pad10)") (class "Default")
      (node (ref "GPIO") (pin "10") (pinfunction "10_10") (pintype "passive"))
    )
  )
)
